# SCH_Potentiometer_Led_MCP3008_2025-05-04.net
KiCad netlist of a schematic drawn in EasyEDA
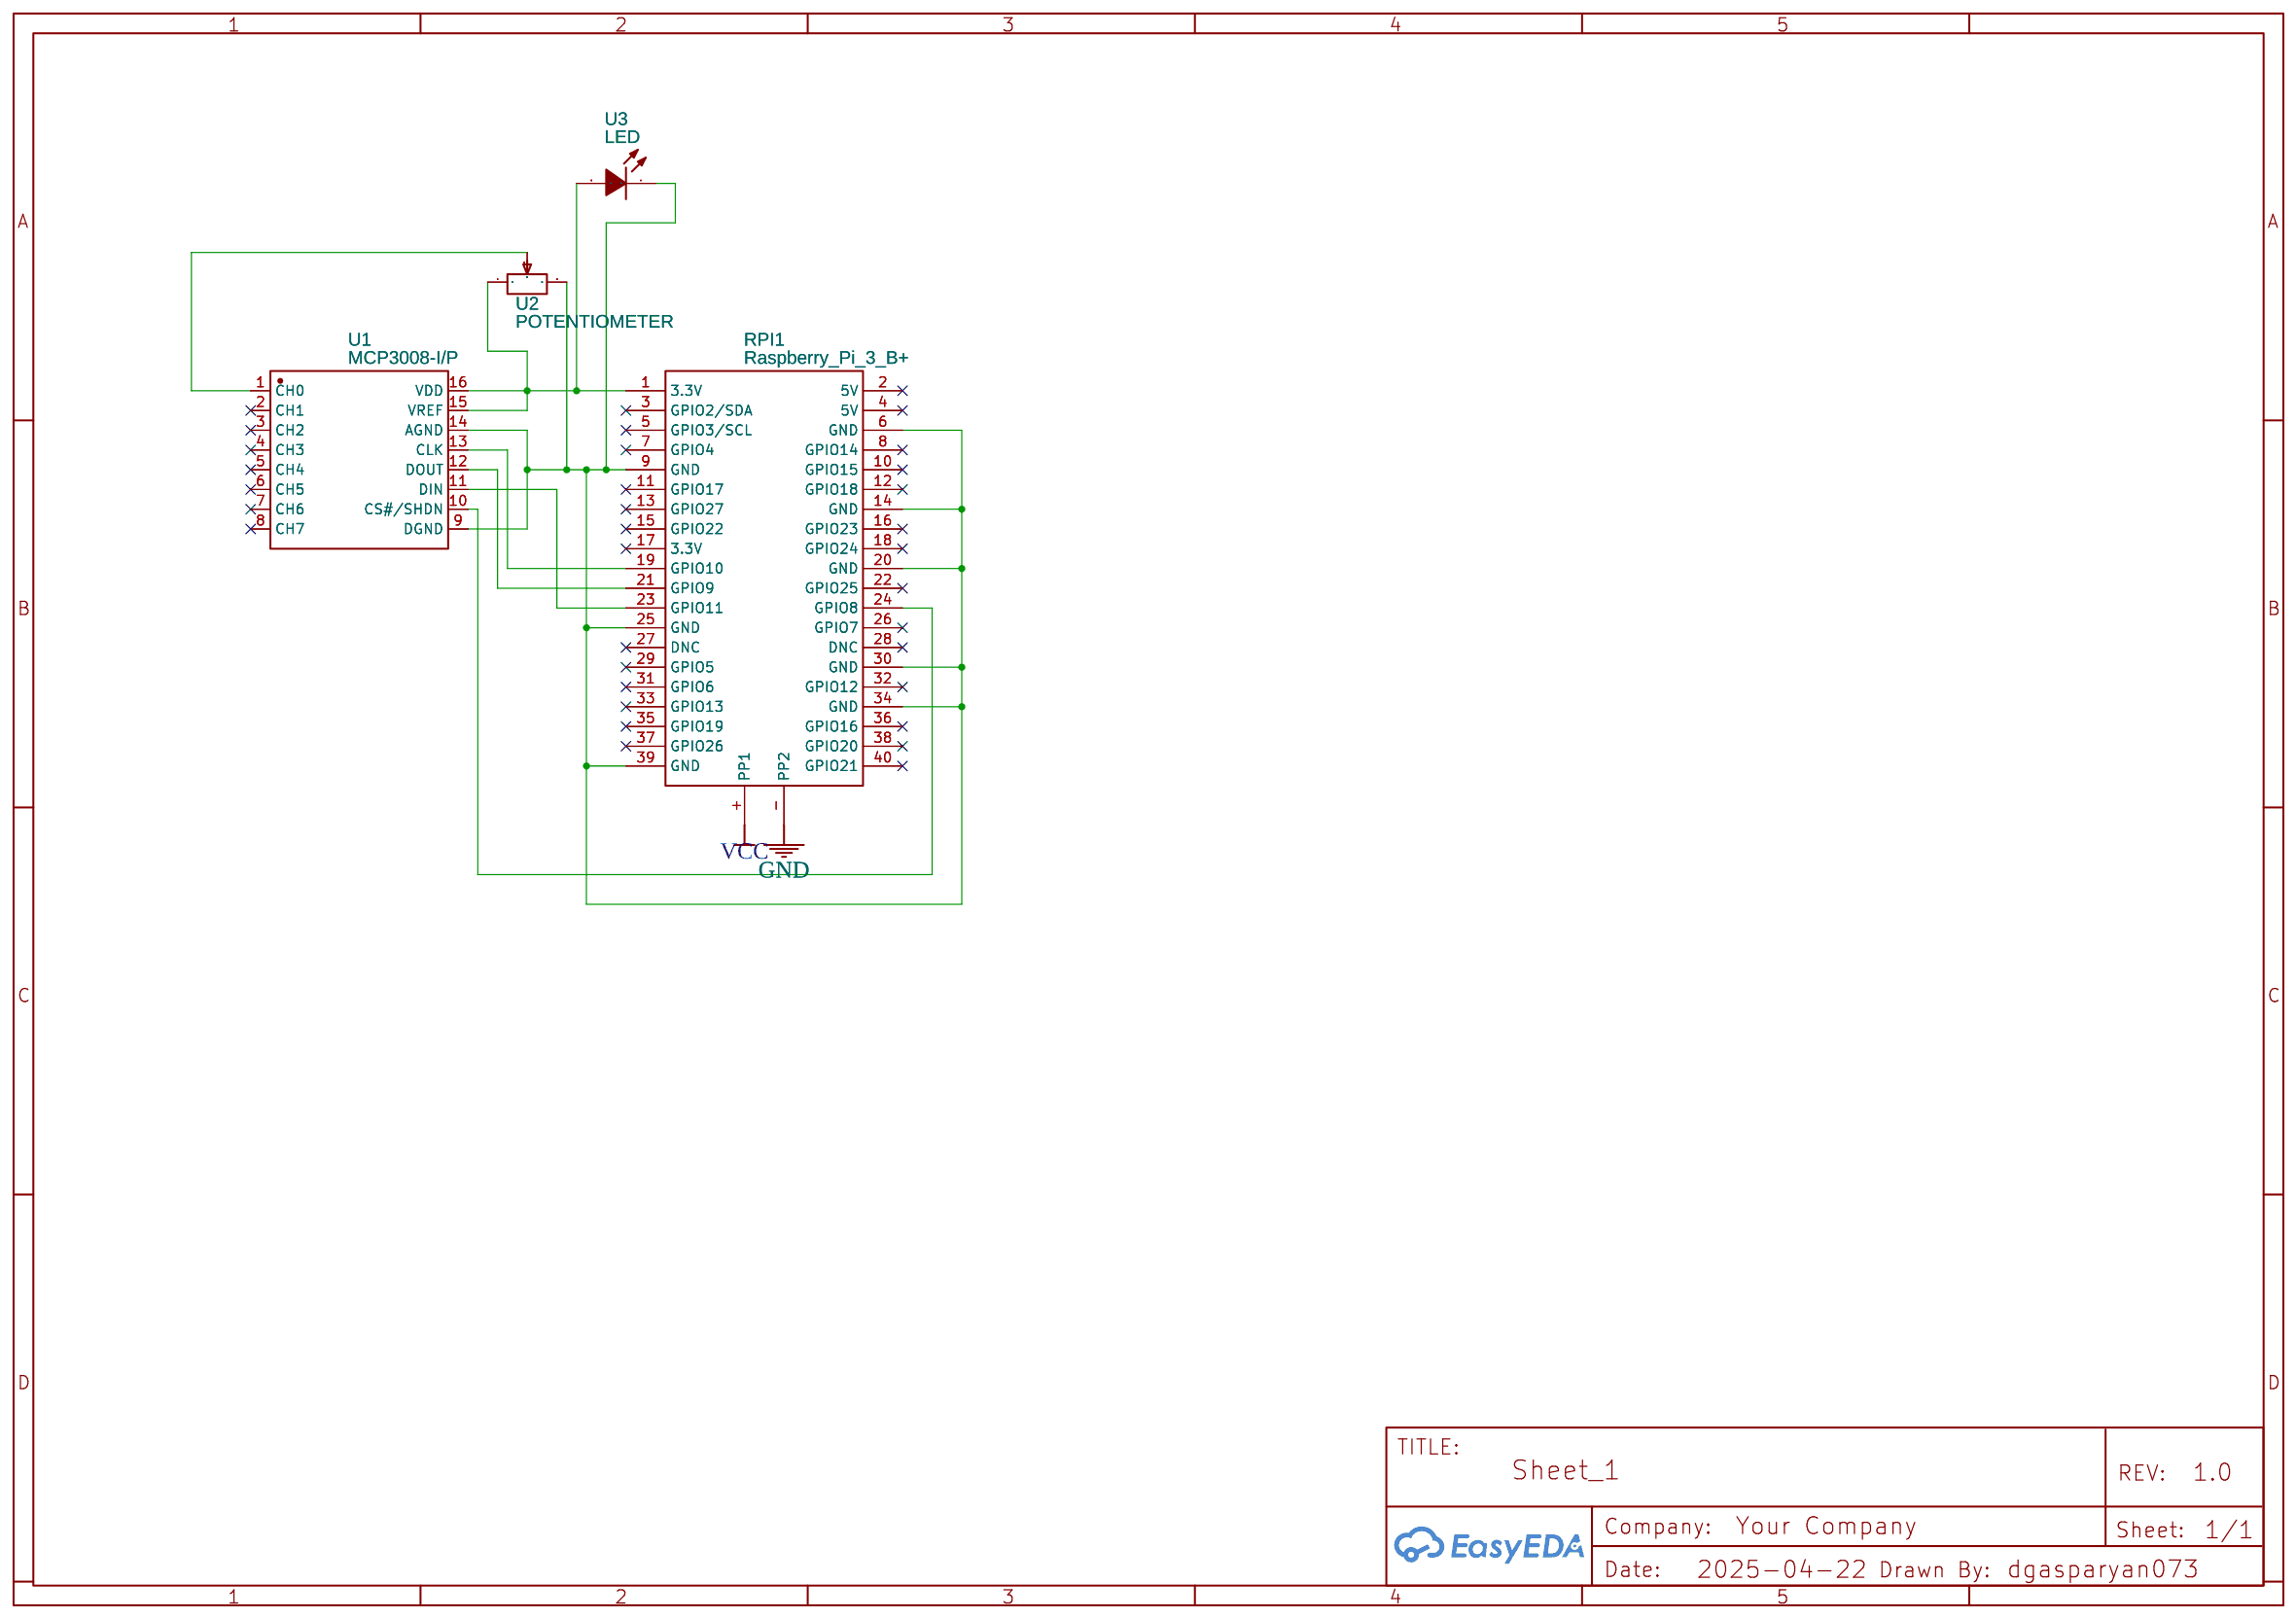
[diagram p0: schematic sheet]

(export (version "E")
  (design (tool "Eeschema 10.0.6"))
  (components
    (comp (ref "RPI1")
      (value "Raspberry_Pi_3_B+")
      (fields
        (field (name "Manufacturer Part") "Raspberry Pi 3 - Model B+ - 1.4GHz Cortex-A53 with 1GB RAM")
        (field (name "Manufacturer") "Raspberry Pi")
      )
      (libsource (lib "") (part "Raspberry_Pi_3_B+"))
    )
    (comp (ref "U1")
      (value "MCP3008-I/P")
      (fields (field (name "Manufacturer") "MICROCHIP(美国微芯)"))
      (libsource (lib "") (part "MCP3008-I/P"))
    )
    (comp (ref "U2")
      (value "POTENTIOMETER")
      (fields (field (name "Manufacturer Part") "3*3Potentiometer-10kΩ20%"))
      (libsource (lib "") (part "3*3POTENTIOMETER-10KΩ20%"))
    )
    (comp (ref "U3")
      (value "LED")
      (fields (field (name "Manufacturer Part") "720-LCGH9RNMXNX1"))
      (libsource (lib "") (part "720-LCGH9RNMXNX1"))
    )
  )
  (nets
    (net (code "1") (name "GND") (class "Default")
      (node (ref "RPI1") (pin "-") (pinfunction "PP2_-") (pintype "unspecified"))
    )
    (net (code "2") (name "Net-(RPI1-GPIO8)") (class "Default")
      (node (ref "RPI1") (pin "24") (pinfunction "GPIO8_24") (pintype "bidirectional"))
      (node (ref "U1") (pin "10") (pinfunction "CS#/SHDN_10") (pintype "unspecified"))
    )
    (net (code "3") (name "Net-(RPI1-GPIO9)") (class "Default")
      (node (ref "RPI1") (pin "21") (pinfunction "GPIO9_21") (pintype "bidirectional"))
      (node (ref "U1") (pin "12") (pinfunction "DOUT_12") (pintype "unspecified"))
    )
    (net (code "4") (name "Net-(RPI1-GPIO10)") (class "Default")
      (node (ref "RPI1") (pin "19") (pinfunction "GPIO10_19") (pintype "bidirectional"))
      (node (ref "U1") (pin "13") (pinfunction "CLK_13") (pintype "unspecified"))
    )
    (net (code "5") (name "Net-(RPI1-GPIO11)") (class "Default")
      (node (ref "RPI1") (pin "23") (pinfunction "GPIO11_23") (pintype "bidirectional"))
      (node (ref "U1") (pin "11") (pinfunction "DIN_11") (pintype "unspecified"))
    )
    (net (code "6") (name "Net-(U1-AGND)") (class "Default")
      (node (ref "RPI1") (pin "14") (pinfunction "GND_14") (pintype "unspecified"))
      (node (ref "RPI1") (pin "20") (pinfunction "GND_20") (pintype "unspecified"))
      (node (ref "RPI1") (pin "25") (pinfunction "GND_25") (pintype "unspecified"))
      (node (ref "RPI1") (pin "30") (pinfunction "GND_30") (pintype "unspecified"))
      (node (ref "RPI1") (pin "34") (pinfunction "GND_34") (pintype "unspecified"))
      (node (ref "RPI1") (pin "39") (pinfunction "GND_39") (pintype "unspecified"))
      (node (ref "RPI1") (pin "6") (pinfunction "GND_6") (pintype "unspecified"))
      (node (ref "RPI1") (pin "9") (pinfunction "GND_9") (pintype "unspecified"))
      (node (ref "U1") (pin "14") (pinfunction "AGND_14") (pintype "unspecified"))
      (node (ref "U1") (pin "9") (pinfunction "DGND_9") (pintype "unspecified"))
      (node (ref "U2") (pin "3") (pinfunction "3_3") (pintype "input"))
      (node (ref "U3") (pin "1") (pinfunction "K_1") (pintype "unspecified"))
    )
    (net (code "7") (name "Net-(U1-CH0)") (class "Default")
      (node (ref "U1") (pin "1") (pinfunction "CH0_1") (pintype "unspecified"))
      (node (ref "U2") (pin "2") (pinfunction "2_2") (pintype "input"))
    )
    (net (code "8") (name "Net-(U1-VDD)") (class "Default")
      (node (ref "RPI1") (pin "1") (pinfunction "3.3V_1") (pintype "passive"))
      (node (ref "U1") (pin "15") (pinfunction "VREF_15") (pintype "unspecified"))
      (node (ref "U1") (pin "16") (pinfunction "VDD_16") (pintype "unspecified"))
      (node (ref "U2") (pin "1") (pinfunction "1_1") (pintype "input"))
      (node (ref "U3") (pin "2") (pinfunction "A_2") (pintype "unspecified"))
    )
    (net (code "9") (name "VCC") (class "Default")
      (node (ref "RPI1") (pin "+") (pinfunction "PP1_+") (pintype "unspecified"))
    )
    (net (code "10") (name "unconnected-(RPI1-3.3V-Pad17)") (class "Default")
      (node (ref "RPI1") (pin "17") (pinfunction "3.3V_17") (pintype "passive+no_connect"))
    )
    (net (code "11") (name "unconnected-(RPI1-5V-Pad2)") (class "Default")
      (node (ref "RPI1") (pin "2") (pinfunction "5V_2") (pintype "passive+no_connect"))
    )
    (net (code "12") (name "unconnected-(RPI1-5V-Pad4)") (class "Default")
      (node (ref "RPI1") (pin "4") (pinfunction "5V_4") (pintype "passive+no_connect"))
    )
    (net (code "13") (name "unconnected-(RPI1-DNC-Pad27)") (class "Default")
      (node (ref "RPI1") (pin "27") (pinfunction "DNC_27") (pintype "unspecified+no_connect"))
    )
    (net (code "14") (name "unconnected-(RPI1-DNC-Pad28)") (class "Default")
      (node (ref "RPI1") (pin "28") (pinfunction "DNC_28") (pintype "unspecified+no_connect"))
    )
    (net (code "15") (name "unconnected-(RPI1-GPIO2{slash}SDA-Pad3)") (class "Default")
      (node (ref "RPI1") (pin "3") (pinfunction "GPIO2/SDA_3") (pintype "bidirectional+no_connect"))
    )
    (net (code "16") (name "unconnected-(RPI1-GPIO3{slash}SCL-Pad5)") (class "Default")
      (node (ref "RPI1") (pin "5") (pinfunction "GPIO3/SCL_5") (pintype "bidirectional+no_connect"))
    )
    (net (code "17") (name "unconnected-(RPI1-GPIO4-Pad7)") (class "Default")
      (node (ref "RPI1") (pin "7") (pinfunction "GPIO4_7") (pintype "bidirectional+no_connect"))
    )
    (net (code "18") (name "unconnected-(RPI1-GPIO5-Pad29)") (class "Default")
      (node (ref "RPI1") (pin "29") (pinfunction "GPIO5_29") (pintype "bidirectional+no_connect"))
    )
    (net (code "19") (name "unconnected-(RPI1-GPIO6-Pad31)") (class "Default")
      (node (ref "RPI1") (pin "31") (pinfunction "GPIO6_31") (pintype "bidirectional+no_connect"))
    )
    (net (code "20") (name "unconnected-(RPI1-GPIO7-Pad26)") (class "Default")
      (node (ref "RPI1") (pin "26") (pinfunction "GPIO7_26") (pintype "bidirectional+no_connect"))
    )
    (net (code "21") (name "unconnected-(RPI1-GPIO12-Pad32)") (class "Default")
      (node (ref "RPI1") (pin "32") (pinfunction "GPIO12_32") (pintype "bidirectional+no_connect"))
    )
    (net (code "22") (name "unconnected-(RPI1-GPIO13-Pad33)") (class "Default")
      (node (ref "RPI1") (pin "33") (pinfunction "GPIO13_33") (pintype "bidirectional+no_connect"))
    )
    (net (code "23") (name "unconnected-(RPI1-GPIO14-Pad8)") (class "Default")
      (node (ref "RPI1") (pin "8") (pinfunction "GPIO14_8") (pintype "bidirectional+no_connect"))
    )
    (net (code "24") (name "unconnected-(RPI1-GPIO15-Pad10)") (class "Default")
      (node (ref "RPI1") (pin "10") (pinfunction "GPIO15_10") (pintype "bidirectional+no_connect"))
    )
    (net (code "25") (name "unconnected-(RPI1-GPIO16-Pad36)") (class "Default")
      (node (ref "RPI1") (pin "36") (pinfunction "GPIO16_36") (pintype "bidirectional+no_connect"))
    )
    (net (code "26") (name "unconnected-(RPI1-GPIO17-Pad11)") (class "Default")
      (node (ref "RPI1") (pin "11") (pinfunction "GPIO17_11") (pintype "bidirectional+no_connect"))
    )
    (net (code "27") (name "unconnected-(RPI1-GPIO18-Pad12)") (class "Default")
      (node (ref "RPI1") (pin "12") (pinfunction "GPIO18_12") (pintype "bidirectional+no_connect"))
    )
    (net (code "28") (name "unconnected-(RPI1-GPIO19-Pad35)") (class "Default")
      (node (ref "RPI1") (pin "35") (pinfunction "GPIO19_35") (pintype "bidirectional+no_connect"))
    )
    (net (code "29") (name "unconnected-(RPI1-GPIO20-Pad38)") (class "Default")
      (node (ref "RPI1") (pin "38") (pinfunction "GPIO20_38") (pintype "bidirectional+no_connect"))
    )
    (net (code "30") (name "unconnected-(RPI1-GPIO21-Pad40)") (class "Default")
      (node (ref "RPI1") (pin "40") (pinfunction "GPIO21_40") (pintype "bidirectional+no_connect"))
    )
    (net (code "31") (name "unconnected-(RPI1-GPIO22-Pad15)") (class "Default")
      (node (ref "RPI1") (pin "15") (pinfunction "GPIO22_15") (pintype "bidirectional+no_connect"))
    )
    (net (code "32") (name "unconnected-(RPI1-GPIO23-Pad16)") (class "Default")
      (node (ref "RPI1") (pin "16") (pinfunction "GPIO23_16") (pintype "bidirectional+no_connect"))
    )
    (net (code "33") (name "unconnected-(RPI1-GPIO24-Pad18)") (class "Default")
      (node (ref "RPI1") (pin "18") (pinfunction "GPIO24_18") (pintype "bidirectional+no_connect"))
    )
    (net (code "34") (name "unconnected-(RPI1-GPIO25-Pad22)") (class "Default")
      (node (ref "RPI1") (pin "22") (pinfunction "GPIO25_22") (pintype "bidirectional+no_connect"))
    )
    (net (code "35") (name "unconnected-(RPI1-GPIO26-Pad37)") (class "Default")
      (node (ref "RPI1") (pin "37") (pinfunction "GPIO26_37") (pintype "bidirectional+no_connect"))
    )
    (net (code "36") (name "unconnected-(RPI1-GPIO27-Pad13)") (class "Default")
      (node (ref "RPI1") (pin "13") (pinfunction "GPIO27_13") (pintype "bidirectional+no_connect"))
    )
    (net (code "37") (name "unconnected-(U1-CH1-Pad2)") (class "Default")
      (node (ref "U1") (pin "2") (pinfunction "CH1_2") (pintype "unspecified+no_connect"))
    )
    (net (code "38") (name "unconnected-(U1-CH2-Pad3)") (class "Default")
      (node (ref "U1") (pin "3") (pinfunction "CH2_3") (pintype "unspecified+no_connect"))
    )
    (net (code "39") (name "unconnected-(U1-CH3-Pad4)") (class "Default")
      (node (ref "U1") (pin "4") (pinfunction "CH3_4") (pintype "unspecified+no_connect"))
    )
    (net (code "40") (name "unconnected-(U1-CH4-Pad5)") (class "Default")
      (node (ref "U1") (pin "5") (pinfunction "CH4_5") (pintype "unspecified+no_connect"))
    )
    (net (code "41") (name "unconnected-(U1-CH5-Pad6)") (class "Default")
      (node (ref "U1") (pin "6") (pinfunction "CH5_6") (pintype "unspecified+no_connect"))
    )
    (net (code "42") (name "unconnected-(U1-CH6-Pad7)") (class "Default")
      (node (ref "U1") (pin "7") (pinfunction "CH6_7") (pintype "unspecified+no_connect"))
    )
    (net (code "43") (name "unconnected-(U1-CH7-Pad8)") (class "Default")
      (node (ref "U1") (pin "8") (pinfunction "CH7_8") (pintype "unspecified+no_connect"))
    )
  )
)
